# LedExtensionBoard_x12.net
KiCad netlist of a schematic drawn in EAGLE
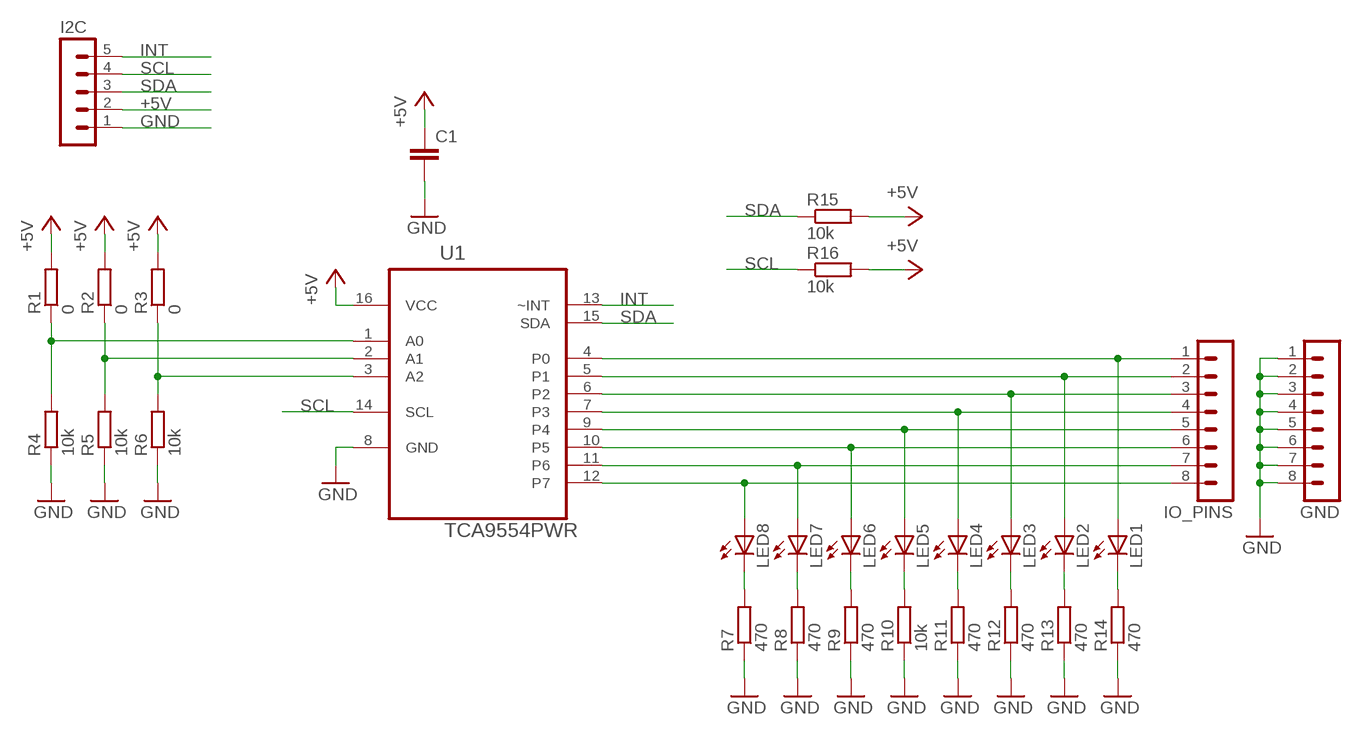
[diagram p0: schematic, sheet 1]

(export (version "E")
  (design (tool "Eeschema 10.0.6"))
  (components
    (comp (ref "C1")
      (value "C-EUC0805")
      (footprint "eagle-import:C0805")
      (libsource (lib "eagle-import") (part "C-EUC0805"))
    )
    (comp (ref "GND")
      (value "MA08-1")
      (footprint "eagle-import:MA08-1")
      (libsource (lib "eagle-import") (part "MA08-1"))
    )
    (comp (ref "I2C")
      (value "MA05-1")
      (footprint "eagle-import:MA05-1")
      (libsource (lib "eagle-import") (part "MA05-1"))
    )
    (comp (ref "IO_PINS")
      (value "MA08-1")
      (footprint "eagle-import:MA08-1")
      (libsource (lib "eagle-import") (part "MA08-1"))
    )
    (comp (ref "LED1")
      (value "LEDSML0805")
      (footprint "eagle-import:SML0805")
      (libsource (lib "eagle-import") (part "LEDSML0805"))
    )
    (comp (ref "LED2")
      (value "LEDSML0805")
      (footprint "eagle-import:SML0805")
      (libsource (lib "eagle-import") (part "LEDSML0805"))
    )
    (comp (ref "LED3")
      (value "LEDSML0805")
      (footprint "eagle-import:SML0805")
      (libsource (lib "eagle-import") (part "LEDSML0805"))
    )
    (comp (ref "LED4")
      (value "LEDSML0805")
      (footprint "eagle-import:SML0805")
      (libsource (lib "eagle-import") (part "LEDSML0805"))
    )
    (comp (ref "LED5")
      (value "LEDSML0805")
      (footprint "eagle-import:SML0805")
      (libsource (lib "eagle-import") (part "LEDSML0805"))
    )
    (comp (ref "LED6")
      (value "LEDSML0805")
      (footprint "eagle-import:SML0805")
      (libsource (lib "eagle-import") (part "LEDSML0805"))
    )
    (comp (ref "LED7")
      (value "LEDSML0805")
      (footprint "eagle-import:SML0805")
      (libsource (lib "eagle-import") (part "LEDSML0805"))
    )
    (comp (ref "LED8")
      (value "LEDSML0805")
      (footprint "eagle-import:SML0805")
      (libsource (lib "eagle-import") (part "LEDSML0805"))
    )
    (comp (ref "R1")
      (value "0")
      (footprint "eagle-import:M1206")
      (libsource (lib "eagle-import") (part "R-EU_M1206"))
    )
    (comp (ref "R2")
      (value "0")
      (footprint "eagle-import:M1206")
      (libsource (lib "eagle-import") (part "R-EU_M1206"))
    )
    (comp (ref "R3")
      (value "0")
      (footprint "eagle-import:M1206")
      (libsource (lib "eagle-import") (part "R-EU_M1206"))
    )
    (comp (ref "R4")
      (value "10k")
      (footprint "eagle-import:M0805")
      (libsource (lib "eagle-import") (part "R-EU_M0805"))
    )
    (comp (ref "R5")
      (value "10k")
      (footprint "eagle-import:M0805")
      (libsource (lib "eagle-import") (part "R-EU_M0805"))
    )
    (comp (ref "R6")
      (value "10k")
      (footprint "eagle-import:M0805")
      (libsource (lib "eagle-import") (part "R-EU_M0805"))
    )
    (comp (ref "R7")
      (value "470")
      (footprint "eagle-import:M0805")
      (libsource (lib "eagle-import") (part "R-EU_M0805"))
    )
    (comp (ref "R8")
      (value "470")
      (footprint "eagle-import:M0805")
      (libsource (lib "eagle-import") (part "R-EU_M0805"))
    )
    (comp (ref "R9")
      (value "470")
      (footprint "eagle-import:M0805")
      (libsource (lib "eagle-import") (part "R-EU_M0805"))
    )
    (comp (ref "R10")
      (value "10k")
      (footprint "eagle-import:M0805")
      (libsource (lib "eagle-import") (part "R-EU_M0805"))
    )
    (comp (ref "R11")
      (value "470")
      (footprint "eagle-import:M0805")
      (libsource (lib "eagle-import") (part "R-EU_M0805"))
    )
    (comp (ref "R12")
      (value "470")
      (footprint "eagle-import:M0805")
      (libsource (lib "eagle-import") (part "R-EU_M0805"))
    )
    (comp (ref "R13")
      (value "470")
      (footprint "eagle-import:M0805")
      (libsource (lib "eagle-import") (part "R-EU_M0805"))
    )
    (comp (ref "R14")
      (value "470")
      (footprint "eagle-import:M0805")
      (libsource (lib "eagle-import") (part "R-EU_M0805"))
    )
    (comp (ref "R15")
      (value "10k")
      (footprint "eagle-import:M0805")
      (libsource (lib "eagle-import") (part "R-EU_M0805"))
    )
    (comp (ref "R16")
      (value "10k")
      (footprint "eagle-import:M0805")
      (libsource (lib "eagle-import") (part "R-EU_M0805"))
    )
    (comp (ref "U1")
      (value "TCA9554PWR")
      (footprint "eagle-import:SOP65P640X120-16N")
      (fields (field (name "MF") "Texas Instruments"))
      (libsource (lib "eagle-import") (part "TCA9554PWR"))
    )
  )
  (nets
    (net (code "1") (name "+5V") (class "Default")
      (node (ref "C1") (pin "1") (pinfunction "1_1") (pintype "passive"))
      (node (ref "I2C") (pin "2") (pinfunction "2_2") (pintype "passive"))
      (node (ref "R1") (pin "2") (pinfunction "2_2") (pintype "passive"))
      (node (ref "R15") (pin "2") (pinfunction "2_2") (pintype "passive"))
      (node (ref "R16") (pin "2") (pinfunction "2_2") (pintype "passive"))
      (node (ref "R2") (pin "2") (pinfunction "2_2") (pintype "passive"))
      (node (ref "R3") (pin "2") (pinfunction "2_2") (pintype "passive"))
      (node (ref "U1") (pin "16") (pinfunction "VCC_16") (pintype "power_in"))
    )
    (net (code "2") (name "/INT") (class "Default")
      (node (ref "I2C") (pin "5") (pinfunction "5_5") (pintype "passive"))
      (node (ref "U1") (pin "13") (pinfunction "~{INT}_13") (pintype "output"))
    )
    (net (code "3") (name "/SCL") (class "Default")
      (node (ref "I2C") (pin "4") (pinfunction "4_4") (pintype "passive"))
      (node (ref "R16") (pin "1") (pinfunction "1_1") (pintype "passive"))
      (node (ref "U1") (pin "14") (pinfunction "SCL_14") (pintype "input"))
    )
    (net (code "4") (name "/SDA") (class "Default")
      (node (ref "I2C") (pin "3") (pinfunction "3_3") (pintype "passive"))
      (node (ref "R15") (pin "1") (pinfunction "1_1") (pintype "passive"))
      (node (ref "U1") (pin "15") (pinfunction "SDA_15") (pintype "bidirectional"))
    )
    (net (code "5") (name "GND") (class "Default")
      (node (ref "C1") (pin "2") (pinfunction "2_2") (pintype "passive"))
      (node (ref "GND") (pin "1") (pinfunction "1_1") (pintype "passive"))
      (node (ref "GND") (pin "2") (pinfunction "2_2") (pintype "passive"))
      (node (ref "GND") (pin "3") (pinfunction "3_3") (pintype "passive"))
      (node (ref "GND") (pin "4") (pinfunction "4_4") (pintype "passive"))
      (node (ref "GND") (pin "5") (pinfunction "5_5") (pintype "passive"))
      (node (ref "GND") (pin "6") (pinfunction "6_6") (pintype "passive"))
      (node (ref "GND") (pin "7") (pinfunction "7_7") (pintype "passive"))
      (node (ref "GND") (pin "8") (pinfunction "8_8") (pintype "passive"))
      (node (ref "I2C") (pin "1") (pinfunction "1_1") (pintype "passive"))
      (node (ref "R10") (pin "1") (pinfunction "1_1") (pintype "passive"))
      (node (ref "R11") (pin "1") (pinfunction "1_1") (pintype "passive"))
      (node (ref "R12") (pin "1") (pinfunction "1_1") (pintype "passive"))
      (node (ref "R13") (pin "1") (pinfunction "1_1") (pintype "passive"))
      (node (ref "R14") (pin "1") (pinfunction "1_1") (pintype "passive"))
      (node (ref "R4") (pin "1") (pinfunction "1_1") (pintype "passive"))
      (node (ref "R5") (pin "1") (pinfunction "1_1") (pintype "passive"))
      (node (ref "R6") (pin "1") (pinfunction "1_1") (pintype "passive"))
      (node (ref "R7") (pin "1") (pinfunction "1_1") (pintype "passive"))
      (node (ref "R8") (pin "1") (pinfunction "1_1") (pintype "passive"))
      (node (ref "R9") (pin "1") (pinfunction "1_1") (pintype "passive"))
      (node (ref "U1") (pin "8") (pinfunction "GND_8") (pintype "passive"))
    )
    (net (code "6") (name "Net-(LED1-PadC)") (class "Default")
      (node (ref "LED1") (pin "C") (pinfunction "C_C") (pintype "passive"))
      (node (ref "R14") (pin "2") (pinfunction "2_2") (pintype "passive"))
    )
    (net (code "7") (name "Net-(LED2-PadC)") (class "Default")
      (node (ref "LED2") (pin "C") (pinfunction "C_C") (pintype "passive"))
      (node (ref "R13") (pin "2") (pinfunction "2_2") (pintype "passive"))
    )
    (net (code "8") (name "Net-(LED3-PadC)") (class "Default")
      (node (ref "LED3") (pin "C") (pinfunction "C_C") (pintype "passive"))
      (node (ref "R12") (pin "2") (pinfunction "2_2") (pintype "passive"))
    )
    (net (code "9") (name "Net-(LED4-PadC)") (class "Default")
      (node (ref "LED4") (pin "C") (pinfunction "C_C") (pintype "passive"))
      (node (ref "R11") (pin "2") (pinfunction "2_2") (pintype "passive"))
    )
    (net (code "10") (name "Net-(LED5-PadC)") (class "Default")
      (node (ref "LED5") (pin "C") (pinfunction "C_C") (pintype "passive"))
      (node (ref "R10") (pin "2") (pinfunction "2_2") (pintype "passive"))
    )
    (net (code "11") (name "Net-(LED6-PadC)") (class "Default")
      (node (ref "LED6") (pin "C") (pinfunction "C_C") (pintype "passive"))
      (node (ref "R9") (pin "2") (pinfunction "2_2") (pintype "passive"))
    )
    (net (code "12") (name "Net-(LED7-PadC)") (class "Default")
      (node (ref "LED7") (pin "C") (pinfunction "C_C") (pintype "passive"))
      (node (ref "R8") (pin "2") (pinfunction "2_2") (pintype "passive"))
    )
    (net (code "13") (name "Net-(LED8-PadC)") (class "Default")
      (node (ref "LED8") (pin "C") (pinfunction "C_C") (pintype "passive"))
      (node (ref "R7") (pin "2") (pinfunction "2_2") (pintype "passive"))
    )
    (net (code "14") (name "Net-(U1-A0)") (class "Default")
      (node (ref "R1") (pin "1") (pinfunction "1_1") (pintype "passive"))
      (node (ref "R4") (pin "2") (pinfunction "2_2") (pintype "passive"))
      (node (ref "U1") (pin "1") (pinfunction "A0_1") (pintype "input"))
    )
    (net (code "15") (name "Net-(U1-A1)") (class "Default")
      (node (ref "R2") (pin "1") (pinfunction "1_1") (pintype "passive"))
      (node (ref "R5") (pin "2") (pinfunction "2_2") (pintype "passive"))
      (node (ref "U1") (pin "2") (pinfunction "A1_2") (pintype "input"))
    )
    (net (code "16") (name "Net-(U1-A2)") (class "Default")
      (node (ref "R3") (pin "1") (pinfunction "1_1") (pintype "passive"))
      (node (ref "R6") (pin "2") (pinfunction "2_2") (pintype "passive"))
      (node (ref "U1") (pin "3") (pinfunction "A2_3") (pintype "input"))
    )
    (net (code "17") (name "Net-(U1-P0)") (class "Default")
      (node (ref "IO_PINS") (pin "1") (pinfunction "1_1") (pintype "passive"))
      (node (ref "LED1") (pin "A") (pinfunction "A_A") (pintype "passive"))
      (node (ref "U1") (pin "4") (pinfunction "P0_4") (pintype "bidirectional"))
    )
    (net (code "18") (name "Net-(U1-P1)") (class "Default")
      (node (ref "IO_PINS") (pin "2") (pinfunction "2_2") (pintype "passive"))
      (node (ref "LED2") (pin "A") (pinfunction "A_A") (pintype "passive"))
      (node (ref "U1") (pin "5") (pinfunction "P1_5") (pintype "bidirectional"))
    )
    (net (code "19") (name "Net-(U1-P2)") (class "Default")
      (node (ref "IO_PINS") (pin "3") (pinfunction "3_3") (pintype "passive"))
      (node (ref "LED3") (pin "A") (pinfunction "A_A") (pintype "passive"))
      (node (ref "U1") (pin "6") (pinfunction "P2_6") (pintype "bidirectional"))
    )
    (net (code "20") (name "Net-(U1-P3)") (class "Default")
      (node (ref "IO_PINS") (pin "4") (pinfunction "4_4") (pintype "passive"))
      (node (ref "LED4") (pin "A") (pinfunction "A_A") (pintype "passive"))
      (node (ref "U1") (pin "7") (pinfunction "P3_7") (pintype "bidirectional"))
    )
    (net (code "21") (name "Net-(U1-P4)") (class "Default")
      (node (ref "IO_PINS") (pin "5") (pinfunction "5_5") (pintype "passive"))
      (node (ref "LED5") (pin "A") (pinfunction "A_A") (pintype "passive"))
      (node (ref "U1") (pin "9") (pinfunction "P4_9") (pintype "bidirectional"))
    )
    (net (code "22") (name "Net-(U1-P5)") (class "Default")
      (node (ref "IO_PINS") (pin "6") (pinfunction "6_6") (pintype "passive"))
      (node (ref "LED6") (pin "A") (pinfunction "A_A") (pintype "passive"))
      (node (ref "U1") (pin "10") (pinfunction "P5_10") (pintype "bidirectional"))
    )
    (net (code "23") (name "Net-(U1-P6)") (class "Default")
      (node (ref "IO_PINS") (pin "7") (pinfunction "7_7") (pintype "passive"))
      (node (ref "LED7") (pin "A") (pinfunction "A_A") (pintype "passive"))
      (node (ref "U1") (pin "11") (pinfunction "P6_11") (pintype "bidirectional"))
    )
    (net (code "24") (name "Net-(U1-P7)") (class "Default")
      (node (ref "IO_PINS") (pin "8") (pinfunction "8_8") (pintype "passive"))
      (node (ref "LED8") (pin "A") (pinfunction "A_A") (pintype "passive"))
      (node (ref "U1") (pin "12") (pinfunction "P7_12") (pintype "bidirectional"))
    )
  )
)
